# MCU.net
KiCad netlist of a schematic drawn in Altium Designer
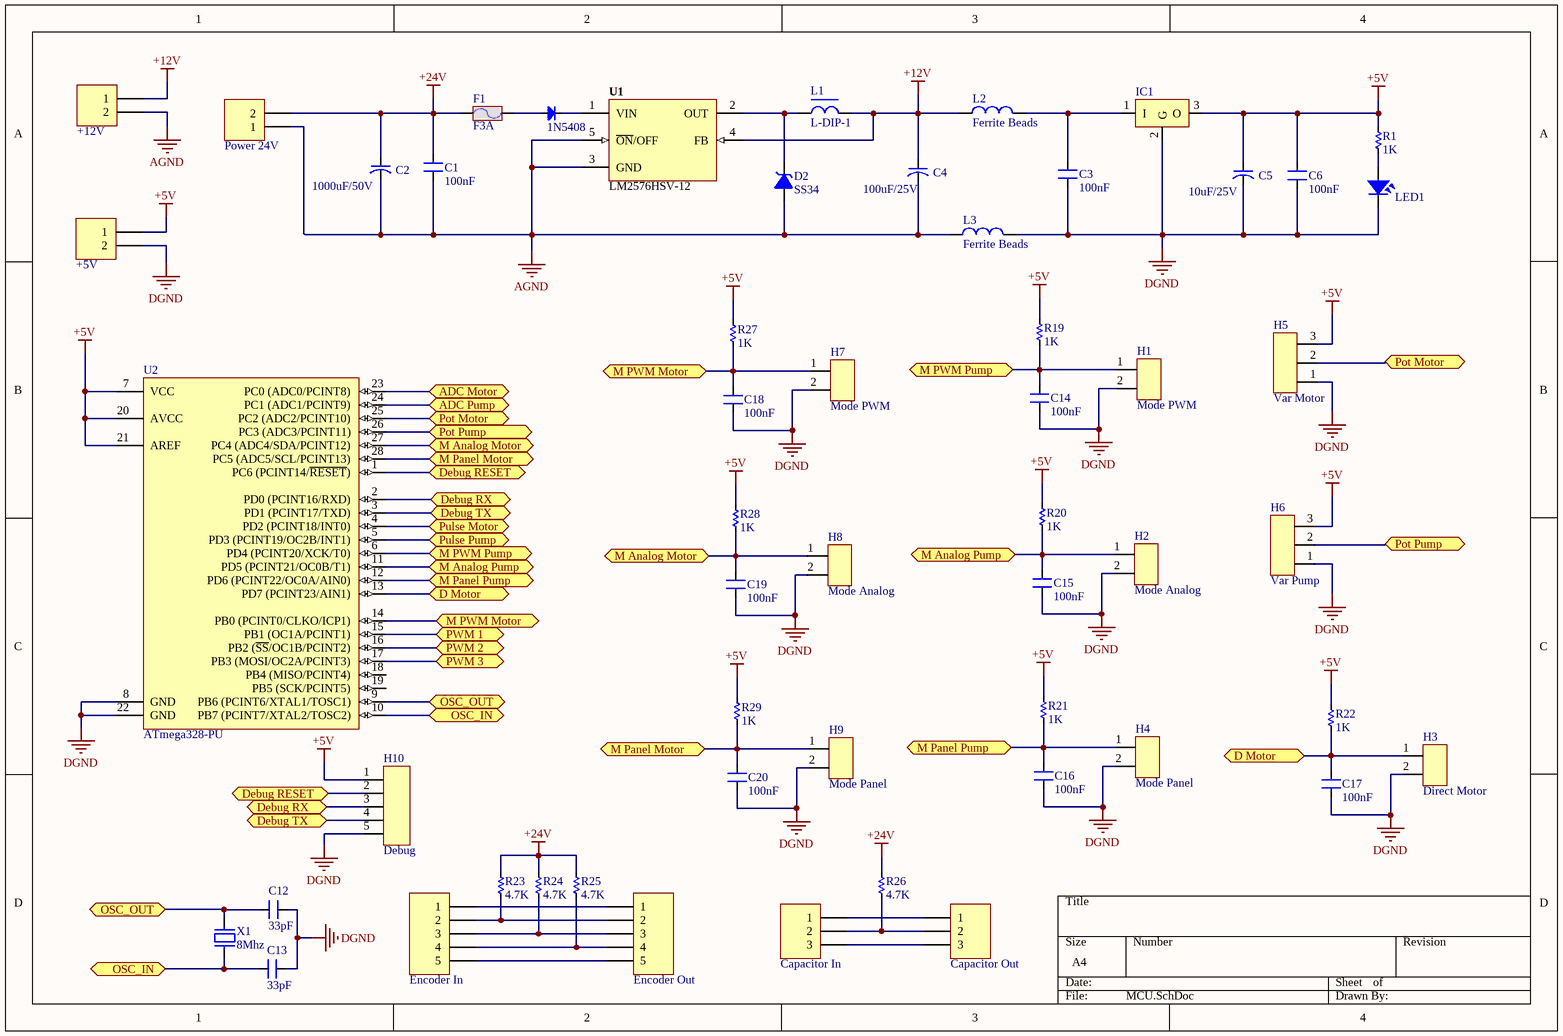
[diagram p0: MCU.SchDoc]

(export (version "E")
  (design (tool "Eeschema 10.0.6"))
  (components
    (comp (ref "+5V")
      (value "Domino 2H")
      (footprint "DOMINO 2-5mm -H")
      (description "Domino 2-Pin, Right Angle")
      (fields (field (name "PUBLISHER") "Altium Limited"))
      (libsource (lib "PIF_Schematic_Lib") (part "Domino 2H"))
    )
    (comp (ref "+12V")
      (value "Domino 2H")
      (footprint "DOMINO 2-5mm -H")
      (description "Domino 2-Pin, Right Angle")
      (fields (field (name "PUBLISHER") "Altium Limited"))
      (libsource (lib "PIF_Schematic_Lib") (part "Domino 2H"))
    )
    (comp (ref "1N5408")
      (value "Diode")
      (footprint "DIO-3A")
      (description "Default Diode")
      (fields (field (name "PUBLISHER") "Altium Limited"))
      (libsource (lib "LIBRARY") (part "Diode"))
    )
    (comp (ref "C1") (value "100nF") (footprint "CN1.5") (libsource (lib "LIBRARY") (part "CN")))
    (comp (ref "C2")
      (value "1000uF/50V")
      (footprint "D12.5xL20")
      (description "DIP Footprint")
      (libsource (lib "BLDC_Libraries") (part "Polary Capacitor"))
    )
    (comp (ref "C3") (value "100nF") (footprint "CN1.5") (libsource (lib "LIBRARY") (part "CN")))
    (comp (ref "C4")
      (value "100uF/25V")
      (footprint "D5xL16")
      (description "DIP Footprint")
      (libsource (lib "BLDC_Libraries") (part "Polary Capacitor"))
    )
    (comp (ref "C5")
      (value "10uF/25V")
      (footprint "D5xL16")
      (description "DIP Footprint")
      (libsource (lib "BLDC_Libraries") (part "Polary Capacitor"))
    )
    (comp (ref "C6") (value "100nF") (footprint "CN1.5") (libsource (lib "LIBRARY") (part "CN")))
    (comp (ref "C12") (value "33pF") (footprint "CN-SMD-0805") (libsource (lib "LIBRARY") (part "CN")))
    (comp (ref "C13") (value "33pF") (footprint "CN-SMD-0805") (libsource (lib "LIBRARY") (part "CN")))
    (comp (ref "C14") (value "100nF") (footprint "CN-SMD-0805") (libsource (lib "LIBRARY") (part "CN")))
    (comp (ref "C15") (value "100nF") (footprint "CN-SMD-0805") (libsource (lib "LIBRARY") (part "CN")))
    (comp (ref "C16") (value "100nF") (footprint "CN-SMD-0805") (libsource (lib "LIBRARY") (part "CN")))
    (comp (ref "C17") (value "100nF") (footprint "CN-SMD-0805") (libsource (lib "LIBRARY") (part "CN")))
    (comp (ref "C18") (value "100nF") (footprint "CN-SMD-0805") (libsource (lib "LIBRARY") (part "CN")))
    (comp (ref "C19") (value "100nF") (footprint "CN-SMD-0805") (libsource (lib "LIBRARY") (part "CN")))
    (comp (ref "C20") (value "100nF") (footprint "CN-SMD-0805") (libsource (lib "LIBRARY") (part "CN")))
    (comp (ref "Capacitor In")
      (value "Domino 3H")
      (footprint "DOMINO 3 - 5mm-H")
      (description "Domino 3-Pin, Right Angle")
      (fields (field (name "PUBLISHER") "Altium Limited"))
      (libsource (lib "PIF_Schematic_Lib") (part "Domino 3H"))
    )
    (comp (ref "Capacitor Out")
      (value "Domino 3H")
      (footprint "DOMINO 3 - 5mm-H")
      (description "Domino 3-Pin, Right Angle")
      (fields (field (name "PUBLISHER") "Altium Limited"))
      (libsource (lib "") (part "Domino 3H_1"))
    )
    (comp (ref "D2") (value "SS34") (footprint "SS34") (libsource (lib "BLDC_Libraries") (part "SS34")))
    (comp (ref "Encoder In")
      (value "Domino 5")
      (footprint "DOMINO 5 - 5mm")
      (description "Domino 5-Pin")
      (fields (field (name "PUBLISHER") "Altium Limited"))
      (libsource (lib "PIF_Schematic_Lib") (part "Domino 5"))
    )
    (comp (ref "Encoder Out")
      (value "Domino 5")
      (footprint "DOMINO 5 - 5mm")
      (description "Domino 5-Pin")
      (fields (field (name "PUBLISHER") "Altium Limited"))
      (libsource (lib "") (part "Domino 5_1"))
    )
    (comp (ref "F1")
      (value "F3A")
      (footprint "Fuse3")
      (description "Fuse")
      (fields (field (name "DESIGNED BY") "VanDungEvn"))
      (libsource (lib "LIBRARY") (part "Fuse"))
    )
    (comp (ref "H1")
      (value "Mode PWM")
      (footprint "Header Bus 2")
      (libsource (lib "BLDC_Libraries") (part "Header 2x1"))
    )
    (comp (ref "H2")
      (value "Mode Analog")
      (footprint "Header Bus 2")
      (libsource (lib "BLDC_Libraries") (part "Header 2x1"))
    )
    (comp (ref "H3")
      (value "Direct Motor")
      (footprint "Header Bus 2")
      (libsource (lib "BLDC_Libraries") (part "Header 2x1"))
    )
    (comp (ref "H4")
      (value "Mode Panel")
      (footprint "Header Bus 2")
      (libsource (lib "BLDC_Libraries") (part "Header 2x1"))
    )
    (comp (ref "H5")
      (value "Var Motor")
      (footprint "Header Bus 3")
      (libsource (lib "BLDC_Libraries") (part "Header 3x1"))
    )
    (comp (ref "H6")
      (value "Var Pump")
      (footprint "Header Bus 3")
      (libsource (lib "BLDC_Libraries") (part "Header 3x1"))
    )
    (comp (ref "H7")
      (value "Mode PWM")
      (footprint "Header Bus 2")
      (libsource (lib "BLDC_Libraries") (part "Header 2x1"))
    )
    (comp (ref "H8")
      (value "Mode Analog")
      (footprint "Header Bus 2")
      (libsource (lib "BLDC_Libraries") (part "Header 2x1"))
    )
    (comp (ref "H9")
      (value "Mode Panel")
      (footprint "Header Bus 2")
      (libsource (lib "BLDC_Libraries") (part "Header 2x1"))
    )
    (comp (ref "H10")
      (value "Debug")
      (footprint "Header 5")
      (libsource (lib "BLDC_Libraries") (part "Header 5x1"))
    )
    (comp (ref "IC1")
      (value "LM78xx")
      (footprint "TO220-123")
      (description "Positive Voltage Regulator")
      (fields (field (name "PUBLISHER") "Altium Limited"))
      (libsource (lib "LIBRARY") (part "LM78xx"))
    )
    (comp (ref "L1")
      (value "L-DIP-1")
      (footprint "L-DIP-M-14x7")
      (description "Inductor")
      (libsource (lib "LIBRARY") (part "L-DIP-1"))
    )
    (comp (ref "L2")
      (value "Ferrite Beads")
      (footprint "RES-SMD-0805")
      (libsource (lib "BLDC_Libraries") (part "Ferrite Beads"))
    )
    (comp (ref "L3")
      (value "Ferrite Beads")
      (footprint "RES-SMD-0805")
      (libsource (lib "BLDC_Libraries") (part "Ferrite Beads"))
    )
    (comp (ref "LED1")
      (value "LED")
      (footprint "LED-0805-Red")
      (description "LED Single colour Green and Red")
      (libsource (lib "LIBRARY") (part "LED"))
    )
    (comp (ref "Power 24V")
      (value "Domino 2H")
      (footprint "DOMINO 2-5mm -H")
      (description "Domino 2-Pin, Right Angle")
      (fields (field (name "PUBLISHER") "Altium Limited"))
      (libsource (lib "") (part "Domino 2H_1"))
    )
    (comp (ref "R1")
      (value "1K")
      (footprint "RES-SMD-0805")
      (description "Res")
      (fields
        (field (name "MANUFACTURER") "Generic Components")
        (field (name "PUBLISHER") "Altium Hobart Technology Centre")
      )
      (libsource (lib "LIBRARY") (part "Res"))
    )
    (comp (ref "R19")
      (value "1K")
      (footprint "RES-SM-0805")
      (description "Res")
      (fields
        (field (name "MANUFACTURER") "Generic Components")
        (field (name "PUBLISHER") "Altium Hobart Technology Centre")
      )
      (libsource (lib "LIBRARY") (part "Res"))
    )
    (comp (ref "R20")
      (value "1K")
      (footprint "RES-SM-0805")
      (description "Res")
      (fields
        (field (name "MANUFACTURER") "Generic Components")
        (field (name "PUBLISHER") "Altium Hobart Technology Centre")
      )
      (libsource (lib "LIBRARY") (part "Res"))
    )
    (comp (ref "R21")
      (value "1K")
      (footprint "RES-SM-0805")
      (description "Res")
      (fields
        (field (name "MANUFACTURER") "Generic Components")
        (field (name "PUBLISHER") "Altium Hobart Technology Centre")
      )
      (libsource (lib "LIBRARY") (part "Res"))
    )
    (comp (ref "R22")
      (value "1K")
      (footprint "RES-SM-0805")
      (description "Res")
      (fields
        (field (name "MANUFACTURER") "Generic Components")
        (field (name "PUBLISHER") "Altium Hobart Technology Centre")
      )
      (libsource (lib "LIBRARY") (part "Res"))
    )
    (comp (ref "R23")
      (value "4.7K")
      (footprint "RES-SM-0805")
      (description "Res")
      (fields
        (field (name "MANUFACTURER") "Generic Components")
        (field (name "PUBLISHER") "Altium Hobart Technology Centre")
      )
      (libsource (lib "LIBRARY") (part "Res"))
    )
    (comp (ref "R24")
      (value "4.7K")
      (footprint "RES-SM-0805")
      (description "Res")
      (fields
        (field (name "MANUFACTURER") "Generic Components")
        (field (name "PUBLISHER") "Altium Hobart Technology Centre")
      )
      (libsource (lib "LIBRARY") (part "Res"))
    )
    (comp (ref "R25")
      (value "4.7K")
      (footprint "RES-SM-0805")
      (description "Res")
      (fields
        (field (name "MANUFACTURER") "Generic Components")
        (field (name "PUBLISHER") "Altium Hobart Technology Centre")
      )
      (libsource (lib "LIBRARY") (part "Res"))
    )
    (comp (ref "R26")
      (value "4.7K")
      (footprint "RES-SM-0805")
      (description "Res")
      (fields
        (field (name "MANUFACTURER") "Generic Components")
        (field (name "PUBLISHER") "Altium Hobart Technology Centre")
      )
      (libsource (lib "LIBRARY") (part "Res"))
    )
    (comp (ref "R27")
      (value "1K")
      (footprint "RES-SM-0805")
      (description "Res")
      (fields
        (field (name "MANUFACTURER") "Generic Components")
        (field (name "PUBLISHER") "Altium Hobart Technology Centre")
      )
      (libsource (lib "LIBRARY") (part "Res"))
    )
    (comp (ref "R28")
      (value "1K")
      (footprint "RES-SM-0805")
      (description "Res")
      (fields
        (field (name "MANUFACTURER") "Generic Components")
        (field (name "PUBLISHER") "Altium Hobart Technology Centre")
      )
      (libsource (lib "LIBRARY") (part "Res"))
    )
    (comp (ref "R29")
      (value "1K")
      (footprint "RES-SM-0805")
      (description "Res")
      (fields
        (field (name "MANUFACTURER") "Generic Components")
        (field (name "PUBLISHER") "Altium Hobart Technology Centre")
      )
      (libsource (lib "LIBRARY") (part "Res"))
    )
    (comp (ref "U1") (value "LM2576HSV-12") (footprint "DIP5") (libsource (lib "LIBRARY") (part "LM2576")))
    (comp (ref "U2")
      (value "ATmega328-PU")
      (footprint "DIP28")
      (fields (field (name "PUBLISHER") "Altium Limited"))
      (libsource (lib "LIBRARY") (part "ATmega328-PU"))
    )
    (comp (ref "X1")
      (value "8Mhz")
      (footprint "XT2-SMD")
      (description "Crystal, 32.768 KHz, -40 to 85 degC, 3.2 x 1.5 x 0.9 mm SMD")
      (libsource (lib "LIBRARY") (part "XT2"))
    )
  )
  (nets
    (net (code "1") (name "+5V") (class "Default")
      (node (ref "+5V") (pin "1") (pinfunction "1_1") (pintype "passive"))
      (node (ref "C5") (pin "1") (pinfunction "1_1") (pintype "passive"))
      (node (ref "C6") (pin "2") (pinfunction "2_2") (pintype "passive"))
      (node (ref "H10") (pin "1") (pinfunction "1_1") (pintype "passive"))
      (node (ref "H5") (pin "3") (pinfunction "3_3") (pintype "passive"))
      (node (ref "H6") (pin "3") (pinfunction "3_3") (pintype "passive"))
      (node (ref "IC1") (pin "3") (pinfunction "O_3") (pintype "power_in"))
      (node (ref "R1") (pin "1") (pinfunction "1_1") (pintype "passive"))
      (node (ref "R19") (pin "1") (pinfunction "1_1") (pintype "passive"))
      (node (ref "R20") (pin "1") (pinfunction "1_1") (pintype "passive"))
      (node (ref "R21") (pin "1") (pinfunction "1_1") (pintype "passive"))
      (node (ref "R22") (pin "1") (pinfunction "1_1") (pintype "passive"))
      (node (ref "R27") (pin "1") (pinfunction "1_1") (pintype "passive"))
      (node (ref "R28") (pin "1") (pinfunction "1_1") (pintype "passive"))
      (node (ref "R29") (pin "1") (pinfunction "1_1") (pintype "passive"))
      (node (ref "U2") (pin "20") (pinfunction "AVCC_20") (pintype "power_in"))
      (node (ref "U2") (pin "21") (pinfunction "AREF_21") (pintype "power_in"))
      (node (ref "U2") (pin "7") (pinfunction "VCC_7") (pintype "power_in"))
    )
    (net (code "2") (name "+12V") (class "Default")
      (node (ref "+12V") (pin "1") (pinfunction "1_1") (pintype "passive"))
      (node (ref "C4") (pin "1") (pinfunction "1_1") (pintype "passive"))
      (node (ref "L1") (pin "2") (pinfunction "2_2") (pintype "passive"))
      (node (ref "L2") (pin "1") (pinfunction "1_1") (pintype "passive"))
      (node (ref "U1") (pin "4") (pinfunction "FB_4") (pintype "input"))
    )
    (net (code "3") (name "+24V") (class "Default")
      (node (ref "C1") (pin "2") (pinfunction "2_2") (pintype "passive"))
      (node (ref "C2") (pin "1") (pinfunction "1_1") (pintype "passive"))
      (node (ref "F1") (pin "1") (pinfunction "1_1") (pintype "passive"))
      (node (ref "Power 24V") (pin "2") (pinfunction "2_2") (pintype "passive"))
      (node (ref "R23") (pin "1") (pinfunction "1_1") (pintype "passive"))
      (node (ref "R24") (pin "1") (pinfunction "1_1") (pintype "passive"))
      (node (ref "R25") (pin "1") (pinfunction "1_1") (pintype "passive"))
      (node (ref "R26") (pin "1") (pinfunction "1_1") (pintype "passive"))
    )
    (net (code "4") (name "/ADC Motor") (class "Default")
      (node (ref "U2") (pin "23") (pinfunction "PC0_(ADC0/PCINT8)_23") (pintype "bidirectional"))
    )
    (net (code "5") (name "/ADC Pump") (class "Default")
      (node (ref "U2") (pin "24") (pinfunction "PC1_(ADC1/PCINT9)_24") (pintype "bidirectional"))
    )
    (net (code "6") (name "/D Motor") (class "Default")
      (node (ref "C17") (pin "2") (pinfunction "2_2") (pintype "passive"))
      (node (ref "H3") (pin "1") (pinfunction "1_1") (pintype "passive"))
      (node (ref "R22") (pin "2") (pinfunction "2_2") (pintype "passive"))
      (node (ref "U2") (pin "13") (pinfunction "PD7_(PCINT23/AIN1)_13") (pintype "bidirectional"))
    )
    (net (code "7") (name "/Debug RESET") (class "Default")
      (node (ref "H10") (pin "2") (pinfunction "2_2") (pintype "passive"))
      (node (ref "U2") (pin "1") (pinfunction "PC6_(PCINT14/~{RESET})_1") (pintype "bidirectional"))
    )
    (net (code "8") (name "/Debug RX") (class "Default")
      (node (ref "H10") (pin "3") (pinfunction "3_3") (pintype "passive"))
      (node (ref "U2") (pin "2") (pinfunction "PD0_(PCINT16/RXD)_2") (pintype "bidirectional"))
    )
    (net (code "9") (name "/Debug TX") (class "Default")
      (node (ref "H10") (pin "4") (pinfunction "4_4") (pintype "passive"))
      (node (ref "U2") (pin "3") (pinfunction "PD1_(PCINT17/TXD)_3") (pintype "bidirectional"))
    )
    (net (code "10") (name "/M Analog Motor") (class "Default")
      (node (ref "C19") (pin "2") (pinfunction "2_2") (pintype "passive"))
      (node (ref "H8") (pin "1") (pinfunction "1_1") (pintype "passive"))
      (node (ref "R28") (pin "2") (pinfunction "2_2") (pintype "passive"))
      (node (ref "U2") (pin "27") (pinfunction "PC4_(ADC4/SDA/PCINT12)_27") (pintype "bidirectional"))
    )
    (net (code "11") (name "/M Analog Pump") (class "Default")
      (node (ref "C15") (pin "2") (pinfunction "2_2") (pintype "passive"))
      (node (ref "H2") (pin "1") (pinfunction "1_1") (pintype "passive"))
      (node (ref "R20") (pin "2") (pinfunction "2_2") (pintype "passive"))
      (node (ref "U2") (pin "11") (pinfunction "PD5_(PCINT21/OC0B/T1)_11") (pintype "bidirectional"))
    )
    (net (code "12") (name "/M PWM Motor") (class "Default")
      (node (ref "C18") (pin "2") (pinfunction "2_2") (pintype "passive"))
      (node (ref "H7") (pin "1") (pinfunction "1_1") (pintype "passive"))
      (node (ref "R27") (pin "2") (pinfunction "2_2") (pintype "passive"))
      (node (ref "U2") (pin "14") (pinfunction "PB0_(PCINT0/CLKO/ICP1)_14") (pintype "bidirectional"))
    )
    (net (code "13") (name "/M PWM Pump") (class "Default")
      (node (ref "C14") (pin "2") (pinfunction "2_2") (pintype "passive"))
      (node (ref "H1") (pin "1") (pinfunction "1_1") (pintype "passive"))
      (node (ref "R19") (pin "2") (pinfunction "2_2") (pintype "passive"))
      (node (ref "U2") (pin "6") (pinfunction "PD4_(PCINT20/XCK/T0)_6") (pintype "bidirectional"))
    )
    (net (code "14") (name "/M Panel Motor") (class "Default")
      (node (ref "C20") (pin "2") (pinfunction "2_2") (pintype "passive"))
      (node (ref "H9") (pin "1") (pinfunction "1_1") (pintype "passive"))
      (node (ref "R29") (pin "2") (pinfunction "2_2") (pintype "passive"))
      (node (ref "U2") (pin "28") (pinfunction "PC5_(ADC5/SCL/PCINT13)_28") (pintype "bidirectional"))
    )
    (net (code "15") (name "/M Panel Pump") (class "Default")
      (node (ref "C16") (pin "2") (pinfunction "2_2") (pintype "passive"))
      (node (ref "H4") (pin "1") (pinfunction "1_1") (pintype "passive"))
      (node (ref "R21") (pin "2") (pinfunction "2_2") (pintype "passive"))
      (node (ref "U2") (pin "12") (pinfunction "PD6_(PCINT22/OC0A/AIN0)_12") (pintype "bidirectional"))
    )
    (net (code "16") (name "/OSC_IN") (class "Default")
      (node (ref "C13") (pin "2") (pinfunction "2_2") (pintype "passive"))
      (node (ref "U2") (pin "10") (pinfunction "PB7_(PCINT7/XTAL2/TOSC2)_10") (pintype "bidirectional"))
      (node (ref "X1") (pin "1") (pinfunction "1_1") (pintype "passive"))
    )
    (net (code "17") (name "/OSC_OUT") (class "Default")
      (node (ref "C12") (pin "2") (pinfunction "2_2") (pintype "passive"))
      (node (ref "U2") (pin "9") (pinfunction "PB6_(PCINT6/XTAL1/TOSC1)_9") (pintype "bidirectional"))
      (node (ref "X1") (pin "2") (pinfunction "2_2") (pintype "passive"))
    )
    (net (code "18") (name "/PWM 1") (class "Default")
      (node (ref "U2") (pin "15") (pinfunction "PB1_(OC1A/PCINT1)_15") (pintype "bidirectional"))
    )
    (net (code "19") (name "/PWM 2") (class "Default")
      (node (ref "U2") (pin "16") (pinfunction "PB2_(~{SS}/OC1B/PCINT2)_16") (pintype "bidirectional"))
    )
    (net (code "20") (name "/PWM 3") (class "Default")
      (node (ref "U2") (pin "17") (pinfunction "PB3_(MOSI/OC2A/PCINT3)_17") (pintype "bidirectional"))
    )
    (net (code "21") (name "/Pot Motor") (class "Default")
      (node (ref "H5") (pin "2") (pinfunction "2_2") (pintype "passive"))
      (node (ref "U2") (pin "25") (pinfunction "PC2_(ADC2/PCINT10)_25") (pintype "bidirectional"))
    )
    (net (code "22") (name "/Pot Pump") (class "Default")
      (node (ref "H6") (pin "2") (pinfunction "2_2") (pintype "passive"))
      (node (ref "U2") (pin "26") (pinfunction "PC3_(ADC3/PCINT11)_26") (pintype "bidirectional"))
    )
    (net (code "23") (name "/Pulse Motor") (class "Default")
      (node (ref "U2") (pin "4") (pinfunction "PD2_(PCINT18/INT0)_4") (pintype "bidirectional"))
    )
    (net (code "24") (name "/Pulse Pump") (class "Default")
      (node (ref "U2") (pin "5") (pinfunction "PD3_(PCINT19/OC2B/INT1)_5") (pintype "bidirectional"))
    )
    (net (code "25") (name "AGND") (class "Default")
      (node (ref "+12V") (pin "2") (pinfunction "2_2") (pintype "passive"))
      (node (ref "C1") (pin "1") (pinfunction "1_1") (pintype "passive"))
      (node (ref "C2") (pin "2") (pinfunction "2_2") (pintype "passive"))
      (node (ref "C4") (pin "2") (pinfunction "2_2") (pintype "passive"))
      (node (ref "D2") (pin "2") (pinfunction "A_2") (pintype "passive"))
      (node (ref "L3") (pin "1") (pinfunction "1_1") (pintype "passive"))
      (node (ref "Power 24V") (pin "1") (pinfunction "1_1") (pintype "passive"))
      (node (ref "U1") (pin "3") (pinfunction "GND_3") (pintype "power_in"))
      (node (ref "U1") (pin "5") (pinfunction "~{ON}/OFF_5") (pintype "input"))
    )
    (net (code "26") (name "DGND") (class "Default")
      (node (ref "+5V") (pin "2") (pinfunction "2_2") (pintype "passive"))
      (node (ref "C12") (pin "1") (pinfunction "1_1") (pintype "passive"))
      (node (ref "C13") (pin "1") (pinfunction "1_1") (pintype "passive"))
      (node (ref "C14") (pin "1") (pinfunction "1_1") (pintype "passive"))
      (node (ref "C15") (pin "1") (pinfunction "1_1") (pintype "passive"))
      (node (ref "C16") (pin "1") (pinfunction "1_1") (pintype "passive"))
      (node (ref "C17") (pin "1") (pinfunction "1_1") (pintype "passive"))
      (node (ref "C18") (pin "1") (pinfunction "1_1") (pintype "passive"))
      (node (ref "C19") (pin "1") (pinfunction "1_1") (pintype "passive"))
      (node (ref "C20") (pin "1") (pinfunction "1_1") (pintype "passive"))
      (node (ref "C3") (pin "1") (pinfunction "1_1") (pintype "passive"))
      (node (ref "C5") (pin "2") (pinfunction "2_2") (pintype "passive"))
      (node (ref "C6") (pin "1") (pinfunction "1_1") (pintype "passive"))
      (node (ref "H1") (pin "2") (pinfunction "2_2") (pintype "passive"))
      (node (ref "H10") (pin "5") (pinfunction "5_5") (pintype "passive"))
      (node (ref "H2") (pin "2") (pinfunction "2_2") (pintype "passive"))
      (node (ref "H3") (pin "2") (pinfunction "2_2") (pintype "passive"))
      (node (ref "H4") (pin "2") (pinfunction "2_2") (pintype "passive"))
      (node (ref "H5") (pin "1") (pinfunction "1_1") (pintype "passive"))
      (node (ref "H6") (pin "1") (pinfunction "1_1") (pintype "passive"))
      (node (ref "H7") (pin "2") (pinfunction "2_2") (pintype "passive"))
      (node (ref "H8") (pin "2") (pinfunction "2_2") (pintype "passive"))
      (node (ref "H9") (pin "2") (pinfunction "2_2") (pintype "passive"))
      (node (ref "IC1") (pin "2") (pinfunction "G_2") (pintype "power_in"))
      (node (ref "L3") (pin "2") (pinfunction "2_2") (pintype "passive"))
      (node (ref "LED1") (pin "2") (pinfunction "2_2") (pintype "passive"))
      (node (ref "U2") (pin "22") (pinfunction "GND_22") (pintype "power_in"))
      (node (ref "U2") (pin "8") (pinfunction "GND_8") (pintype "power_in"))
    )
    (net (code "27") (name "Net-(1N5408-A)") (class "Default")
      (node (ref "1N5408") (pin "1") (pinfunction "A_1") (pintype "passive"))
      (node (ref "F1") (pin "2") (pinfunction "2_2") (pintype "passive"))
    )
    (net (code "28") (name "Net-(1N5408-K)") (class "Default")
      (node (ref "1N5408") (pin "2") (pinfunction "K_2") (pintype "passive"))
      (node (ref "U1") (pin "1") (pinfunction "VIN_1") (pintype "power_in"))
    )
    (net (code "29") (name "Net-(Capacitor In-Pad1)") (class "Default")
      (node (ref "Capacitor In") (pin "1") (pinfunction "1_1") (pintype "passive"))
      (node (ref "Capacitor Out") (pin "1") (pinfunction "1_1") (pintype "passive"))
    )
    (net (code "30") (name "Net-(Capacitor In-Pad2)") (class "Default")
      (node (ref "Capacitor In") (pin "2") (pinfunction "2_2") (pintype "passive"))
      (node (ref "Capacitor Out") (pin "2") (pinfunction "2_2") (pintype "passive"))
      (node (ref "R26") (pin "2") (pinfunction "2_2") (pintype "passive"))
    )
    (net (code "31") (name "Net-(Capacitor In-Pad3)") (class "Default")
      (node (ref "Capacitor In") (pin "3") (pinfunction "3_3") (pintype "passive"))
      (node (ref "Capacitor Out") (pin "3") (pinfunction "3_3") (pintype "passive"))
    )
    (net (code "32") (name "Net-(D2-K)") (class "Default")
      (node (ref "D2") (pin "1") (pinfunction "K_1") (pintype "passive"))
      (node (ref "L1") (pin "1") (pinfunction "1_1") (pintype "passive"))
      (node (ref "U1") (pin "2") (pinfunction "OUT_2") (pintype "power_in"))
    )
    (net (code "33") (name "Net-(Encoder In-Pad1)") (class "Default")
      (node (ref "Encoder In") (pin "1") (pinfunction "1_1") (pintype "passive"))
      (node (ref "Encoder Out") (pin "1") (pinfunction "1_1") (pintype "passive"))
    )
    (net (code "34") (name "Net-(Encoder In-Pad2)") (class "Default")
      (node (ref "Encoder In") (pin "2") (pinfunction "2_2") (pintype "passive"))
      (node (ref "Encoder Out") (pin "2") (pinfunction "2_2") (pintype "passive"))
      (node (ref "R23") (pin "2") (pinfunction "2_2") (pintype "passive"))
    )
    (net (code "35") (name "Net-(Encoder In-Pad3)") (class "Default")
      (node (ref "Encoder In") (pin "3") (pinfunction "3_3") (pintype "passive"))
      (node (ref "Encoder Out") (pin "3") (pinfunction "3_3") (pintype "passive"))
      (node (ref "R24") (pin "2") (pinfunction "2_2") (pintype "passive"))
    )
    (net (code "36") (name "Net-(Encoder In-Pad4)") (class "Default")
      (node (ref "Encoder In") (pin "4") (pinfunction "4_4") (pintype "passive"))
      (node (ref "Encoder Out") (pin "4") (pinfunction "4_4") (pintype "passive"))
      (node (ref "R25") (pin "2") (pinfunction "2_2") (pintype "passive"))
    )
    (net (code "37") (name "Net-(Encoder In-Pad5)") (class "Default")
      (node (ref "Encoder In") (pin "5") (pinfunction "5_5") (pintype "passive"))
      (node (ref "Encoder Out") (pin "5") (pinfunction "5_5") (pintype "passive"))
    )
    (net (code "38") (name "Net-(IC1-I)") (class "Default")
      (node (ref "C3") (pin "2") (pinfunction "2_2") (pintype "passive"))
      (node (ref "IC1") (pin "1") (pinfunction "I_1") (pintype "power_in"))
      (node (ref "L2") (pin "2") (pinfunction "2_2") (pintype "passive"))
    )
    (net (code "39") (name "Net-(LED1-Pad1)") (class "Default")
      (node (ref "LED1") (pin "1") (pinfunction "1_1") (pintype "passive"))
      (node (ref "R1") (pin "2") (pinfunction "2_2") (pintype "passive"))
    )
    (net (code "40") (name "unconnected-(U2-PB4_(MISO{slash}PCINT4)-Pad18)") (class "Default")
      (node (ref "U2") (pin "18") (pinfunction "PB4_(MISO/PCINT4)_18") (pintype "bidirectional"))
    )
    (net (code "41") (name "unconnected-(U2-PB5_(SCK{slash}PCINT5)-Pad19)") (class "Default")
      (node (ref "U2") (pin "19") (pinfunction "PB5_(SCK/PCINT5)_19") (pintype "bidirectional"))
    )
  )
)
